# pCog100_Wifi_Sensor_uSD_TFT.net
KiCad netlist of a schematic drawn in EAGLE
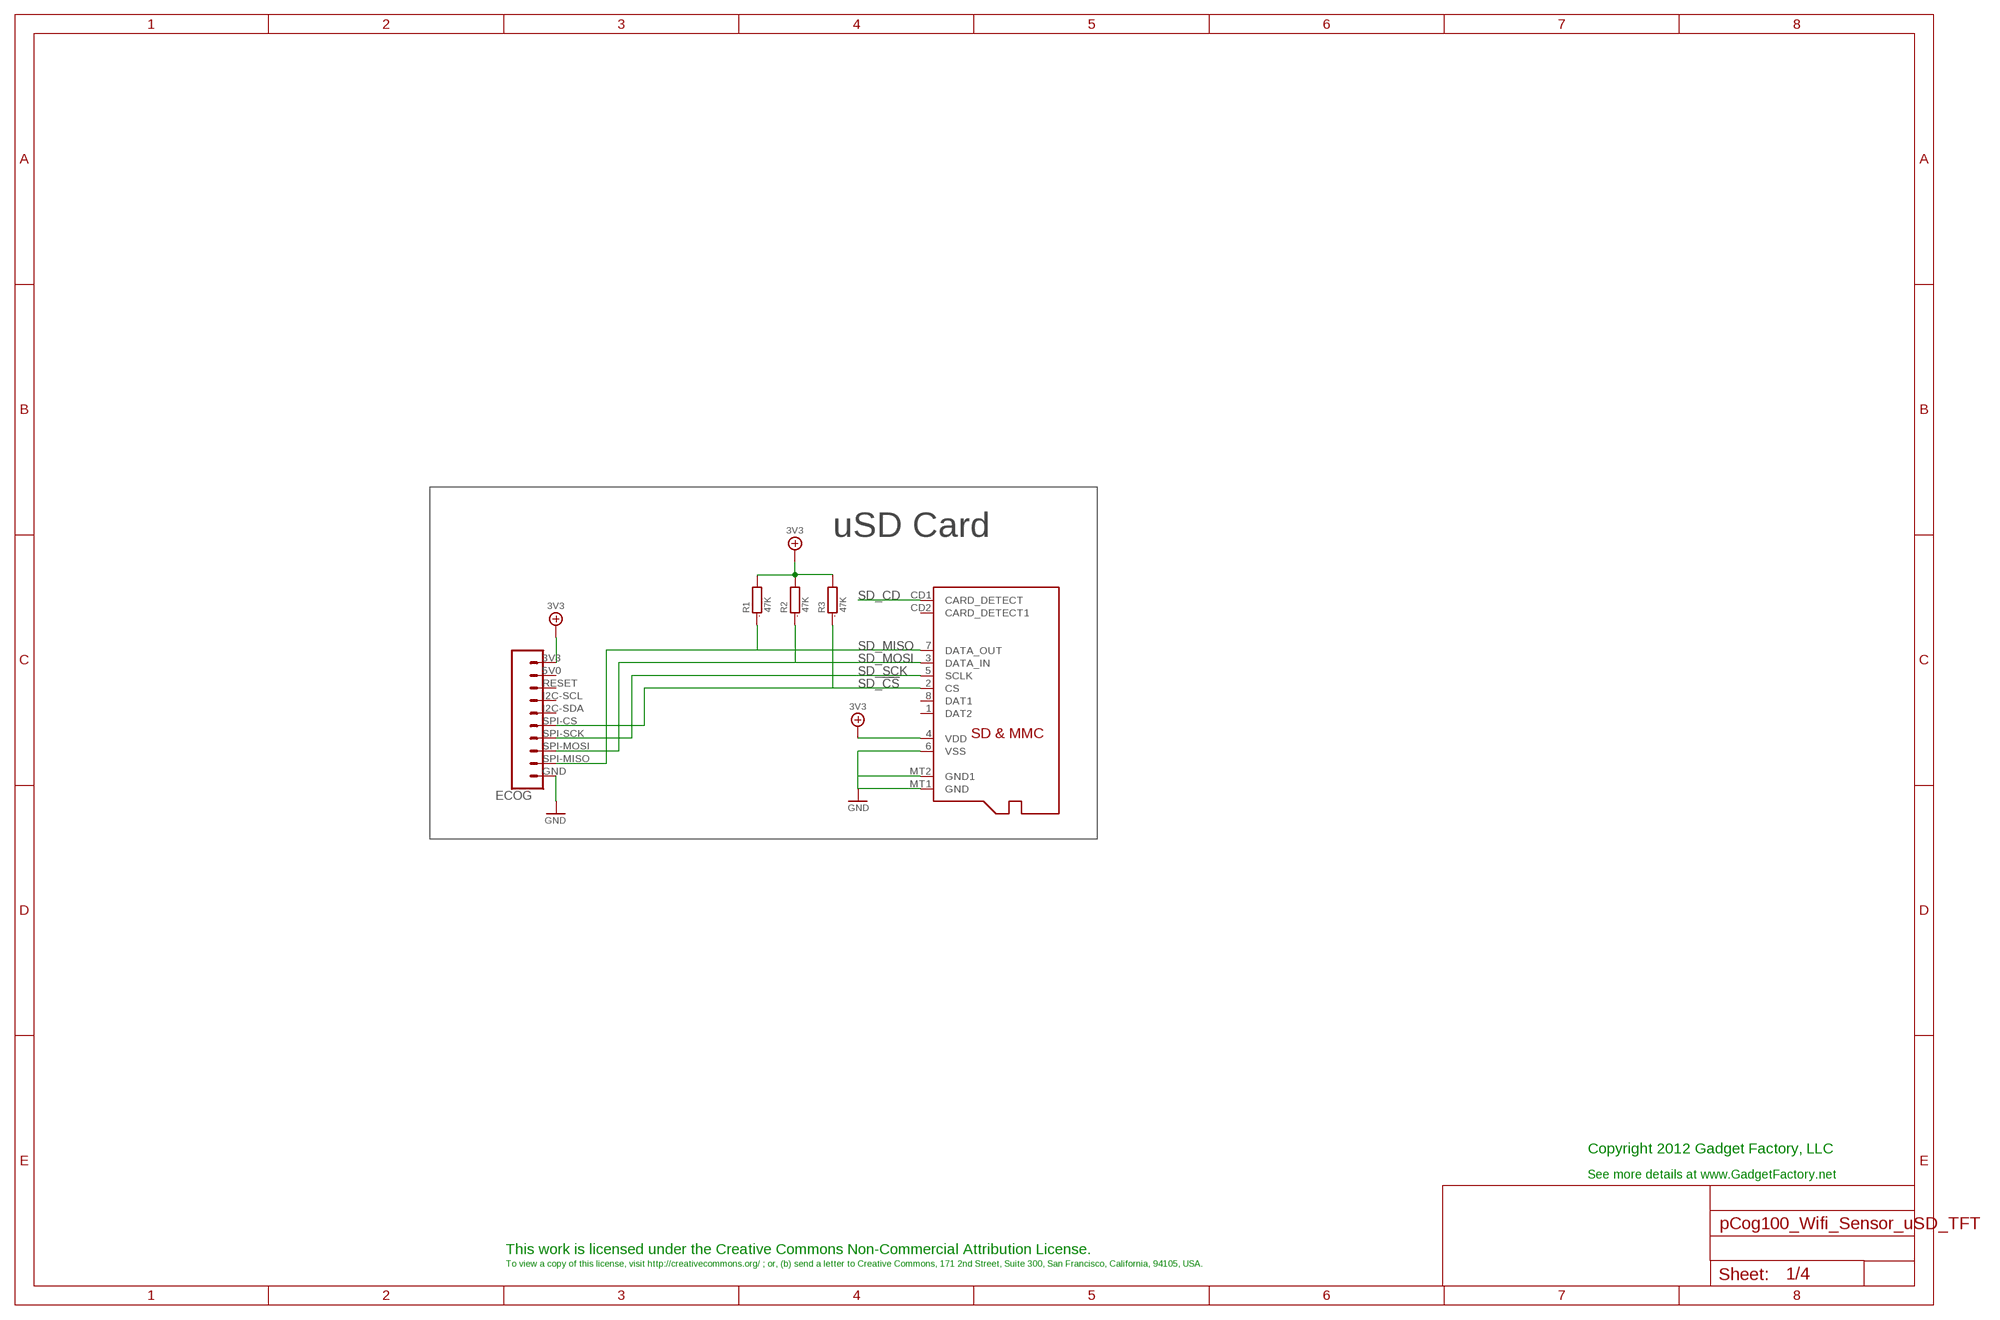
[diagram p0: schematic, sheet 1]
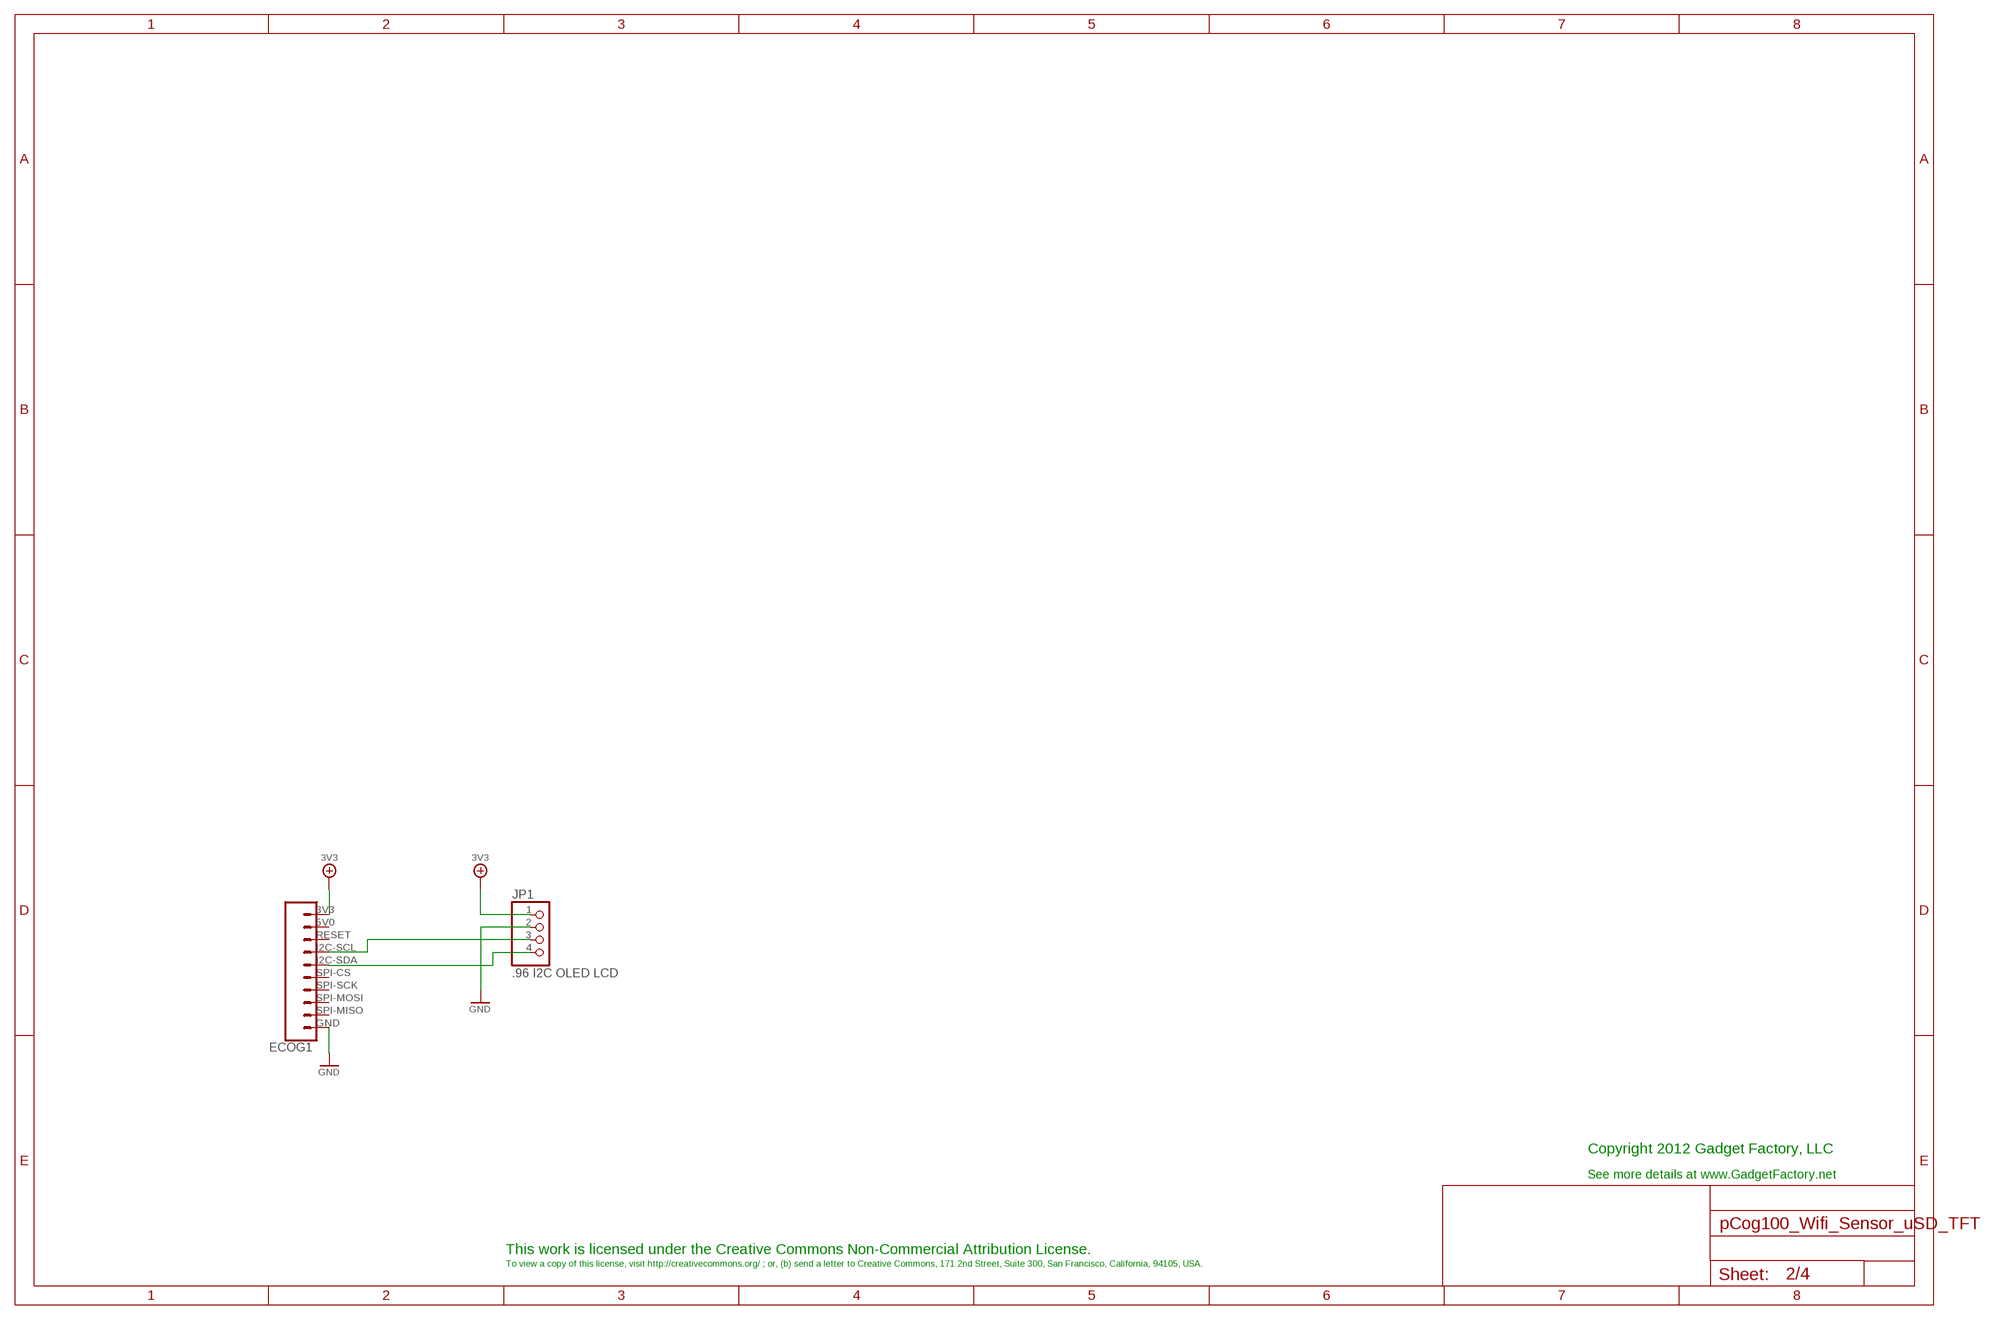
[diagram p1: schematic, sheet 2]
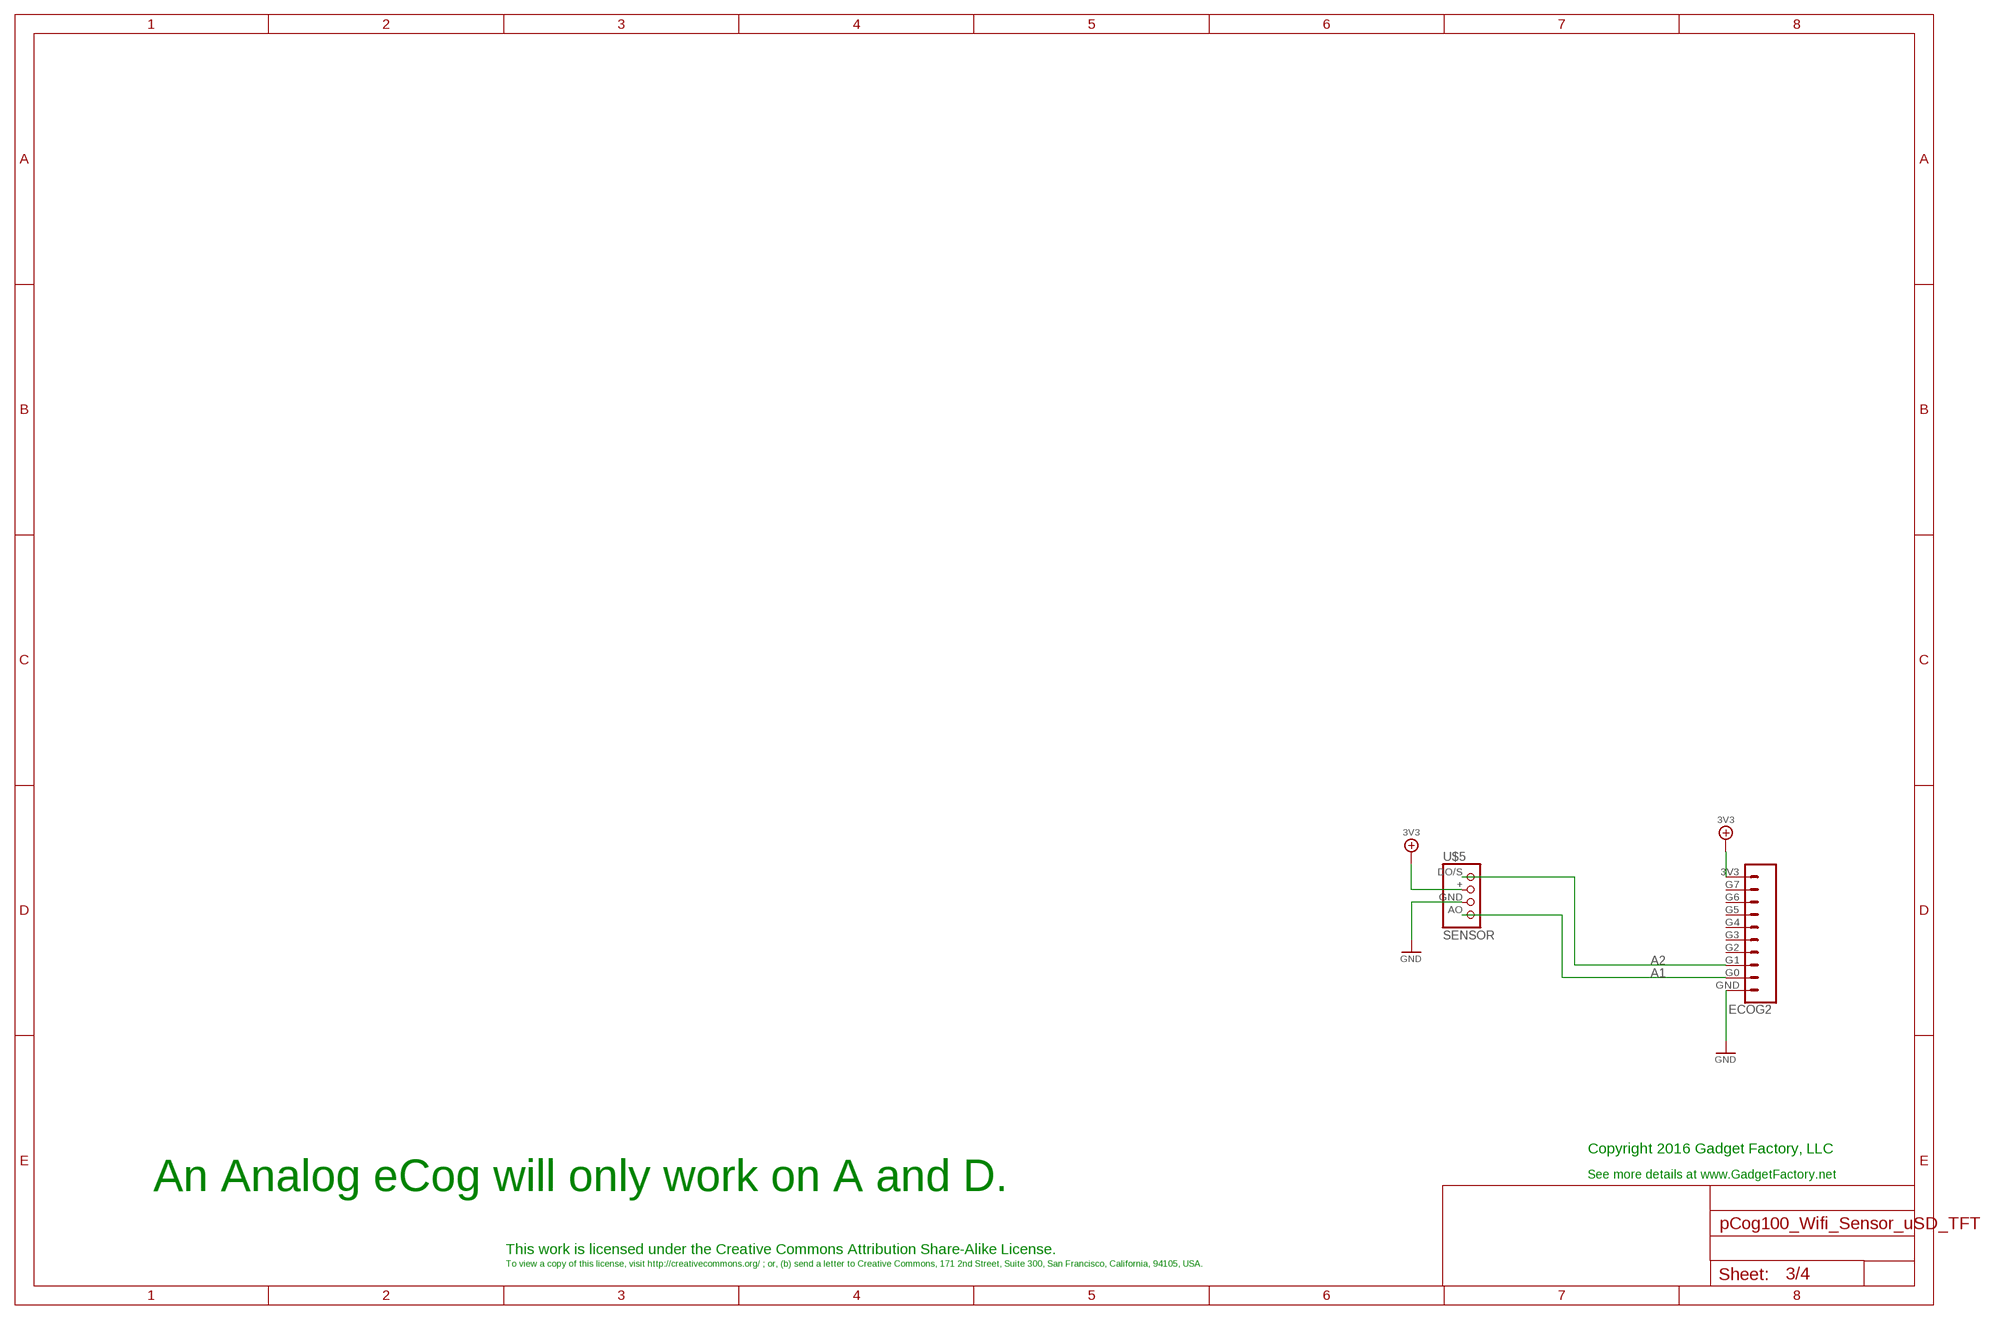
[diagram p2: schematic, sheet 3]
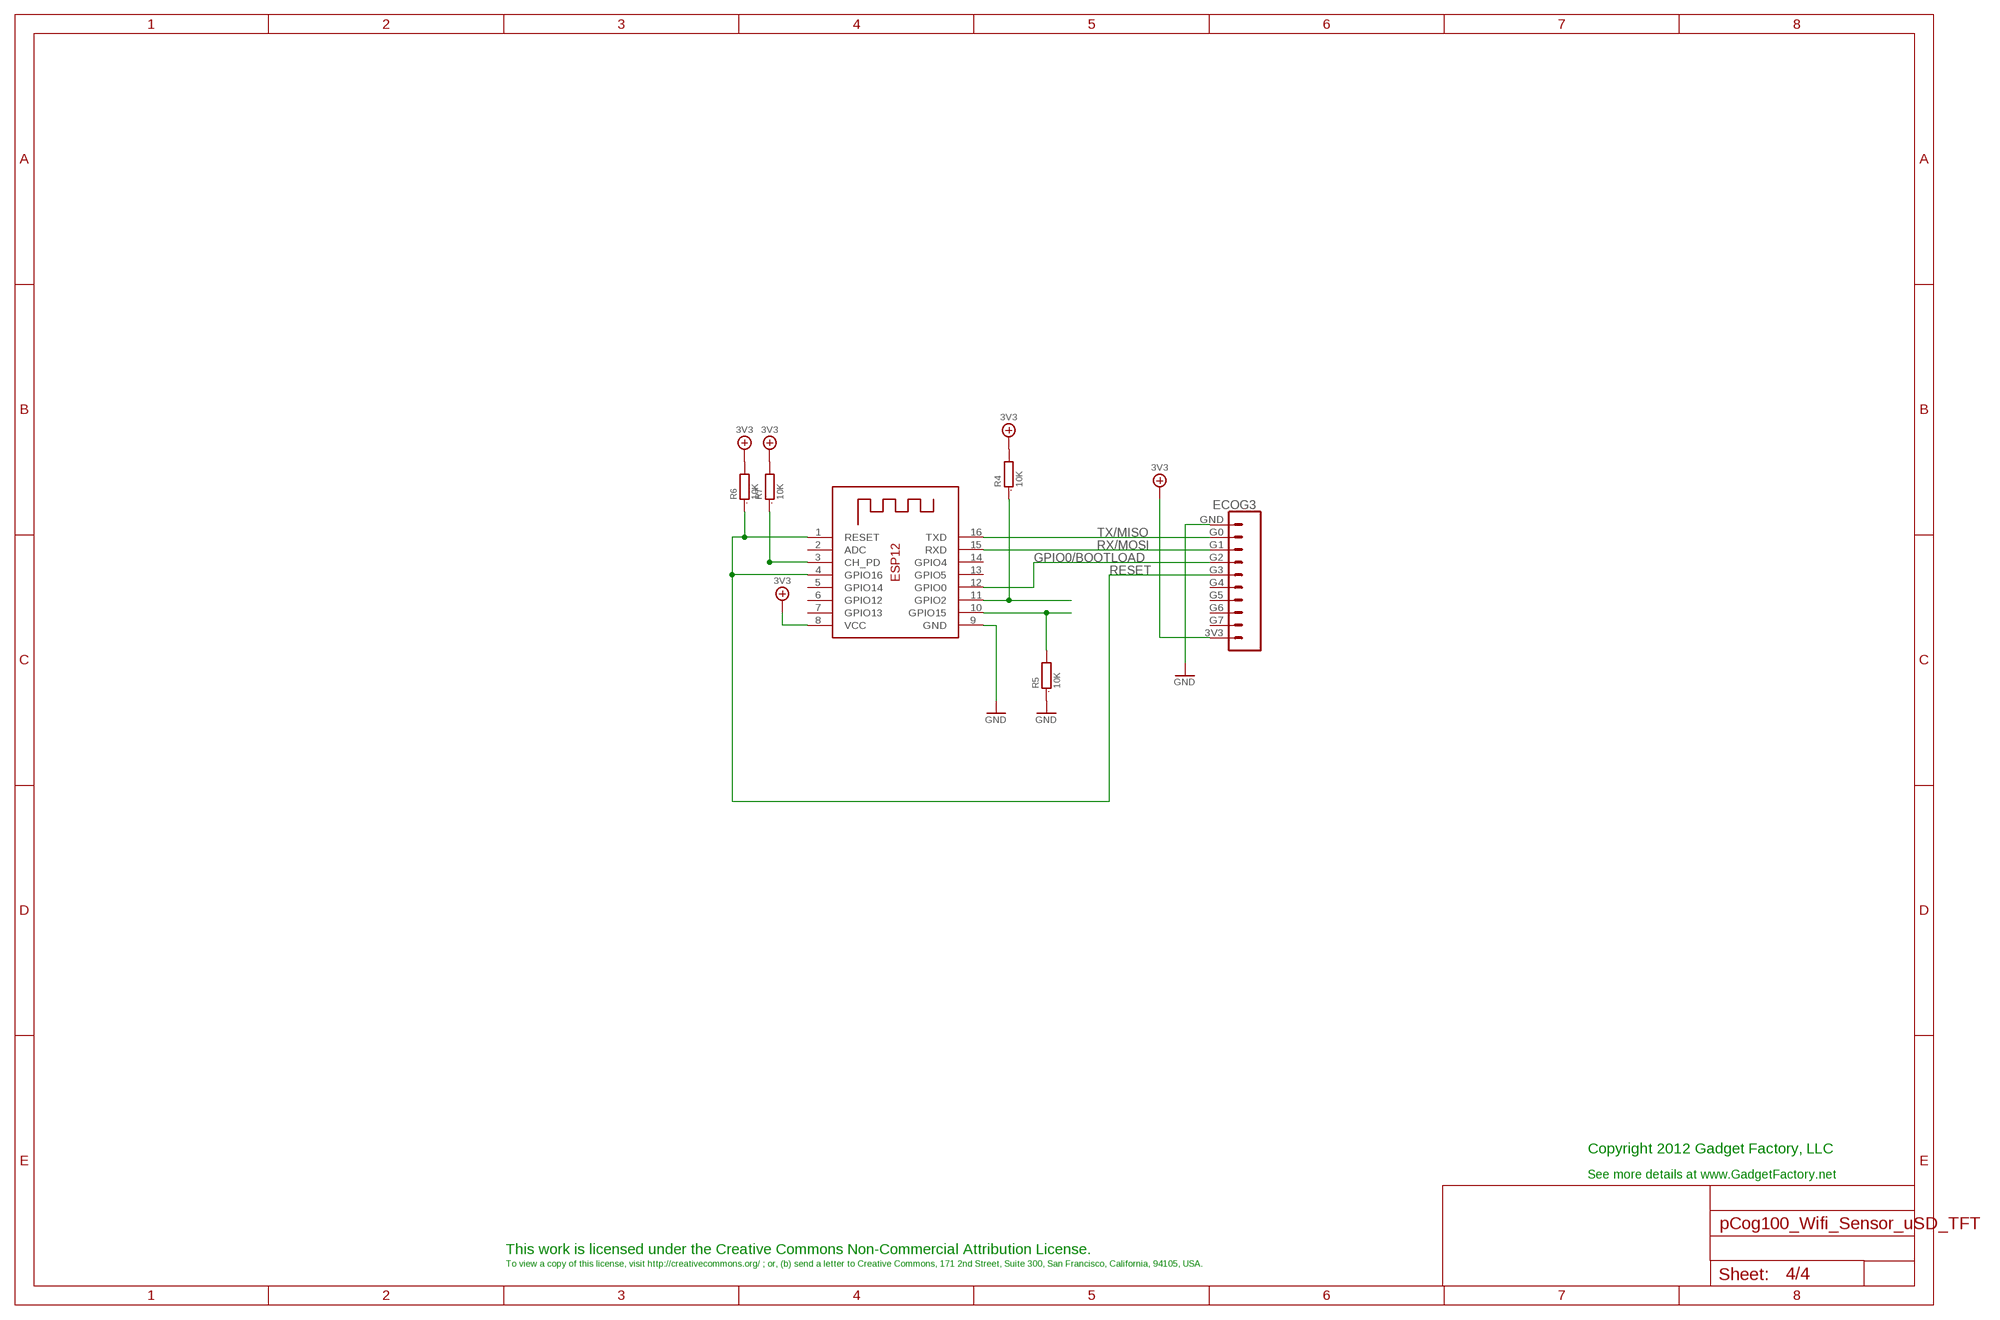
[diagram p3: schematic, sheet 4]

(export (version "E")
  (design (tool "Eeschema 10.0.6"))
  (components
    (comp (ref "ECOG3")
      (value "ECOG_GENERAL_ROWECOG_GENERAL_SMD")
      (footprint "eagle-import:ECOG_GENERAL_SMD")
      (libsource (lib "eagle-import") (part "ECOG_GENERAL_ROWECOG_GENERAL_SMD"))
    )
    (comp (ref "R4")
      (value "10K")
      (footprint "eagle-import:0805")
      (libsource (lib "eagle-import") (part "R0805"))
    )
    (comp (ref "R5")
      (value "10K")
      (footprint "eagle-import:0805")
      (libsource (lib "eagle-import") (part "R0805"))
    )
    (comp (ref "R6")
      (value "10K")
      (footprint "eagle-import:0805")
      (libsource (lib "eagle-import") (part "R0805"))
    )
    (comp (ref "R7")
      (value "10K")
      (footprint "eagle-import:0805")
      (libsource (lib "eagle-import") (part "R0805"))
    )
    (comp (ref "X1")
      (value "ESP-12")
      (footprint "eagle-import:ESP-12")
      (libsource (lib "eagle-import") (part "ESP-12"))
    )
    (comp (ref "ECOG1")
      (value "ECOG_BUSES_ROWECOG_BUSES_SMD")
      (footprint "eagle-import:ECOG_BUSES_SMD")
      (libsource (lib "eagle-import") (part "ECOG_BUSES_ROWECOG_BUSES_SMD"))
    )
    (comp (ref "JP1")
      (value ".96 I2C OLED LCD")
      (footprint "eagle-import:1X04")
      (libsource (lib "eagle-import") (part "PINHD-1X4"))
    )
    (comp (ref "ECOG2")
      (value "ECOG_GENERAL_ROWECOG_GENERAL_SMD")
      (footprint "eagle-import:ECOG_GENERAL_SMD")
      (libsource (lib "eagle-import") (part "ECOG_GENERAL_ROWECOG_GENERAL_SMD"))
    )
    (comp (ref "U$5")
      (value "SENSOR")
      (footprint "eagle-import:SENSOR-HJX4")
      (libsource (lib "eagle-import") (part "SENSOR"))
    )
    (comp (ref "ECOG")
      (value "ECOG_BUSES_ROWECOG_BUSES_SMD")
      (footprint "eagle-import:ECOG_BUSES_SMD")
      (libsource (lib "eagle-import") (part "ECOG_BUSES_ROWECOG_BUSES_SMD"))
    )
    (comp (ref "R1")
      (value "47K")
      (footprint "eagle-import:0805")
      (fields (field (name "PARTNO") "RMCF0805JT47K0"))
      (libsource (lib "eagle-import") (part "GadgetFactory_6.0_R0805"))
    )
    (comp (ref "R2")
      (value "47K")
      (footprint "eagle-import:0805")
      (fields (field (name "PARTNO") "RMCF0805JT47K0"))
      (libsource (lib "eagle-import") (part "GadgetFactory_6.0_R0805"))
    )
    (comp (ref "R3")
      (value "47K")
      (footprint "eagle-import:0805")
      (fields (field (name "PARTNO") "RMCF0805JT47K0"))
      (libsource (lib "eagle-import") (part "GadgetFactory_6.0_R0805"))
    )
    (comp (ref "SD1")
      (value "MICROSD")
      (footprint "eagle-import:MICROSD")
      (fields (field (name "DIGIKEY") "101-00660-68-6-1-ND") (field (name "PARTNO") "101-00660-68-6"))
      (libsource (lib "eagle-import") (part "MICROSD"))
    )
  )
  (nets
    (net (code "1") (name "3V3") (class "Default")
      (node (ref "ECOG") (pin "3V3") (pinfunction "3V3_3V3") (pintype "passive"))
      (node (ref "ECOG1") (pin "3V3") (pinfunction "3V3_3V3") (pintype "passive"))
      (node (ref "ECOG2") (pin "3V3") (pinfunction "3V3_3V3") (pintype "power_in"))
      (node (ref "ECOG3") (pin "3V3") (pinfunction "3V3_3V3") (pintype "power_in"))
      (node (ref "JP1") (pin "1") (pinfunction "1_1") (pintype "passive"))
      (node (ref "R1") (pin "2") (pinfunction "2_2") (pintype "passive"))
      (node (ref "R2") (pin "2") (pinfunction "2_2") (pintype "passive"))
      (node (ref "R3") (pin "2") (pinfunction "2_2") (pintype "passive"))
      (node (ref "R4") (pin "2") (pinfunction "2_2") (pintype "passive"))
      (node (ref "R6") (pin "2") (pinfunction "2_2") (pintype "passive"))
      (node (ref "R7") (pin "2") (pinfunction "2_2") (pintype "passive"))
      (node (ref "SD1") (pin "4") (pinfunction "VDD_4") (pintype "power_in"))
      (node (ref "U$5") (pin "+") (pinfunction "+_+") (pintype "passive"))
      (node (ref "X1") (pin "8") (pinfunction "VCC_8") (pintype "power_in"))
    )
    (net (code "2") (name "A1") (class "Default")
      (node (ref "ECOG2") (pin "G0") (pinfunction "G0_G0") (pintype "passive"))
      (node (ref "U$5") (pin "AO") (pinfunction "AO_AO") (pintype "passive"))
    )
    (net (code "3") (name "A2") (class "Default")
      (node (ref "ECOG2") (pin "G1") (pinfunction "G1_G1") (pintype "passive"))
      (node (ref "U$5") (pin "DO/S") (pinfunction "DO/S_DO/S") (pintype "passive"))
    )
    (net (code "4") (name "GND") (class "Default")
      (node (ref "ECOG") (pin "GND") (pinfunction "GND_GND") (pintype "passive"))
      (node (ref "ECOG1") (pin "GND") (pinfunction "GND_GND") (pintype "passive"))
      (node (ref "ECOG2") (pin "GND") (pinfunction "GND_GND") (pintype "power_in"))
      (node (ref "ECOG3") (pin "GND") (pinfunction "GND_GND") (pintype "power_in"))
      (node (ref "JP1") (pin "2") (pinfunction "2_2") (pintype "passive"))
      (node (ref "R5") (pin "1") (pinfunction "1_1") (pintype "passive"))
      (node (ref "SD1") (pin "6") (pinfunction "VSS_6") (pintype "power_in"))
      (node (ref "SD1") (pin "MT1") (pinfunction "GND_MT1") (pintype "power_in"))
      (node (ref "SD1") (pin "MT2") (pinfunction "GND1_MT2") (pintype "power_in"))
      (node (ref "U$5") (pin "GND") (pinfunction "GND_GND") (pintype "passive"))
      (node (ref "X1") (pin "9") (pinfunction "GND_9") (pintype "power_in"))
    )
    (net (code "5") (name "GPIO0{slash}BOOTLOAD") (class "Default")
      (node (ref "ECOG3") (pin "G2") (pinfunction "G2_G2") (pintype "passive"))
      (node (ref "X1") (pin "12") (pinfunction "GPIO0_12") (pintype "bidirectional"))
    )
    (net (code "6") (name "Net-(ECOG1-PadI2C-SCL)") (class "Default")
      (node (ref "ECOG1") (pin "I2C-SCL") (pinfunction "I2C-SCL_I2C-SCL") (pintype "passive"))
      (node (ref "JP1") (pin "3") (pinfunction "3_3") (pintype "passive"))
    )
    (net (code "7") (name "Net-(ECOG1-PadI2C-SDA)") (class "Default")
      (node (ref "ECOG1") (pin "I2C-SDA") (pinfunction "I2C-SDA_I2C-SDA") (pintype "passive"))
      (node (ref "JP1") (pin "4") (pinfunction "4_4") (pintype "passive"))
    )
    (net (code "8") (name "Net-(X1-CH_PD)") (class "Default")
      (node (ref "R7") (pin "1") (pinfunction "1_1") (pintype "passive"))
      (node (ref "X1") (pin "3") (pinfunction "CH_PD_3") (pintype "input"))
    )
    (net (code "9") (name "Net-(X1-GPIO2)") (class "Default")
      (node (ref "R4") (pin "1") (pinfunction "1_1") (pintype "passive"))
      (node (ref "X1") (pin "11") (pinfunction "GPIO2_11") (pintype "bidirectional"))
    )
    (net (code "10") (name "Net-(X1-GPIO15)") (class "Default")
      (node (ref "R5") (pin "2") (pinfunction "2_2") (pintype "passive"))
      (node (ref "X1") (pin "10") (pinfunction "GPIO15_10") (pintype "bidirectional"))
    )
    (net (code "11") (name "RESET") (class "Default")
      (node (ref "ECOG3") (pin "G3") (pinfunction "G3_G3") (pintype "passive"))
      (node (ref "R6") (pin "1") (pinfunction "1_1") (pintype "passive"))
      (node (ref "X1") (pin "1") (pinfunction "RESET_1") (pintype "input"))
      (node (ref "X1") (pin "4") (pinfunction "GPIO16_4") (pintype "bidirectional"))
    )
    (net (code "12") (name "RX{slash}MOSI") (class "Default")
      (node (ref "ECOG3") (pin "G1") (pinfunction "G1_G1") (pintype "passive"))
      (node (ref "X1") (pin "15") (pinfunction "RXD_15") (pintype "input"))
    )
    (net (code "13") (name "SD_CD") (class "Default")
      (node (ref "SD1") (pin "CD1") (pinfunction "CARD_DETECT_CD1") (pintype "passive"))
    )
    (net (code "14") (name "SD_MISO") (class "Default")
      (node (ref "ECOG") (pin "SPI-MISO") (pinfunction "SPI-MISO_SPI-MISO") (pintype "passive"))
      (node (ref "R1") (pin "1") (pinfunction "1_1") (pintype "passive"))
      (node (ref "SD1") (pin "7") (pinfunction "DATA_OUT_7") (pintype "output"))
    )
    (net (code "15") (name "SD_MOSI") (class "Default")
      (node (ref "ECOG") (pin "SPI-MOSI") (pinfunction "SPI-MOSI_SPI-MOSI") (pintype "passive"))
      (node (ref "R2") (pin "1") (pinfunction "1_1") (pintype "passive"))
      (node (ref "SD1") (pin "3") (pinfunction "DATA_IN_3") (pintype "input"))
    )
    (net (code "16") (name "SD_SCK") (class "Default")
      (node (ref "ECOG") (pin "SPI-SCK") (pinfunction "SPI-SCK_SPI-SCK") (pintype "passive"))
      (node (ref "SD1") (pin "5") (pinfunction "SCLK_5") (pintype "input"))
    )
    (net (code "17") (name "SD_~{CS}") (class "Default")
      (node (ref "ECOG") (pin "SPI-CS") (pinfunction "SPI-CS_SPI-CS") (pintype "passive"))
      (node (ref "R3") (pin "1") (pinfunction "1_1") (pintype "passive"))
      (node (ref "SD1") (pin "2") (pinfunction "CS_2") (pintype "input"))
    )
    (net (code "18") (name "TX{slash}MISO") (class "Default")
      (node (ref "ECOG3") (pin "G0") (pinfunction "G0_G0") (pintype "passive"))
      (node (ref "X1") (pin "16") (pinfunction "TXD_16") (pintype "output"))
    )
    (net (code "19") (name "unconnected-(ECOG-Pad5V0)") (class "Default")
      (node (ref "ECOG") (pin "5V0") (pinfunction "5V0_5V0") (pintype "passive"))
    )
    (net (code "20") (name "unconnected-(ECOG-PadI2C-SCL)") (class "Default")
      (node (ref "ECOG") (pin "I2C-SCL") (pinfunction "I2C-SCL_I2C-SCL") (pintype "passive"))
    )
    (net (code "21") (name "unconnected-(ECOG-PadI2C-SDA)") (class "Default")
      (node (ref "ECOG") (pin "I2C-SDA") (pinfunction "I2C-SDA_I2C-SDA") (pintype "passive"))
    )
    (net (code "22") (name "unconnected-(ECOG-PadRESET)") (class "Default")
      (node (ref "ECOG") (pin "RESET") (pinfunction "RESET_RESET") (pintype "passive"))
    )
    (net (code "23") (name "unconnected-(ECOG1-Pad5V0)") (class "Default")
      (node (ref "ECOG1") (pin "5V0") (pinfunction "5V0_5V0") (pintype "passive"))
    )
    (net (code "24") (name "unconnected-(ECOG1-PadRESET)") (class "Default")
      (node (ref "ECOG1") (pin "RESET") (pinfunction "RESET_RESET") (pintype "passive"))
    )
    (net (code "25") (name "unconnected-(ECOG1-PadSPI-CS)") (class "Default")
      (node (ref "ECOG1") (pin "SPI-CS") (pinfunction "SPI-CS_SPI-CS") (pintype "passive"))
    )
    (net (code "26") (name "unconnected-(ECOG1-PadSPI-MISO)") (class "Default")
      (node (ref "ECOG1") (pin "SPI-MISO") (pinfunction "SPI-MISO_SPI-MISO") (pintype "passive"))
    )
    (net (code "27") (name "unconnected-(ECOG1-PadSPI-MOSI)") (class "Default")
      (node (ref "ECOG1") (pin "SPI-MOSI") (pinfunction "SPI-MOSI_SPI-MOSI") (pintype "passive"))
    )
    (net (code "28") (name "unconnected-(ECOG1-PadSPI-SCK)") (class "Default")
      (node (ref "ECOG1") (pin "SPI-SCK") (pinfunction "SPI-SCK_SPI-SCK") (pintype "passive"))
    )
    (net (code "29") (name "unconnected-(ECOG2-PadG2)") (class "Default")
      (node (ref "ECOG2") (pin "G2") (pinfunction "G2_G2") (pintype "passive"))
    )
    (net (code "30") (name "unconnected-(ECOG2-PadG3)") (class "Default")
      (node (ref "ECOG2") (pin "G3") (pinfunction "G3_G3") (pintype "passive"))
    )
    (net (code "31") (name "unconnected-(ECOG2-PadG4)") (class "Default")
      (node (ref "ECOG2") (pin "G4") (pinfunction "G4_G4") (pintype "passive"))
    )
    (net (code "32") (name "unconnected-(ECOG2-PadG5)") (class "Default")
      (node (ref "ECOG2") (pin "G5") (pinfunction "G5_G5") (pintype "passive"))
    )
    (net (code "33") (name "unconnected-(ECOG2-PadG6)") (class "Default")
      (node (ref "ECOG2") (pin "G6") (pinfunction "G6_G6") (pintype "passive"))
    )
    (net (code "34") (name "unconnected-(ECOG2-PadG7)") (class "Default")
      (node (ref "ECOG2") (pin "G7") (pinfunction "G7_G7") (pintype "passive"))
    )
    (net (code "35") (name "unconnected-(ECOG3-PadG4)") (class "Default")
      (node (ref "ECOG3") (pin "G4") (pinfunction "G4_G4") (pintype "passive"))
    )
    (net (code "36") (name "unconnected-(ECOG3-PadG5)") (class "Default")
      (node (ref "ECOG3") (pin "G5") (pinfunction "G5_G5") (pintype "passive"))
    )
    (net (code "37") (name "unconnected-(ECOG3-PadG6)") (class "Default")
      (node (ref "ECOG3") (pin "G6") (pinfunction "G6_G6") (pintype "passive"))
    )
    (net (code "38") (name "unconnected-(ECOG3-PadG7)") (class "Default")
      (node (ref "ECOG3") (pin "G7") (pinfunction "G7_G7") (pintype "passive"))
    )
    (net (code "39") (name "unconnected-(SD1-CARD_DETECT1-PadCD2)") (class "Default")
      (node (ref "SD1") (pin "CD2") (pinfunction "CARD_DETECT1_CD2") (pintype "passive"))
    )
    (net (code "40") (name "unconnected-(SD1-DAT1-Pad8)") (class "Default")
      (node (ref "SD1") (pin "8") (pinfunction "DAT1_8") (pintype "bidirectional"))
    )
    (net (code "41") (name "unconnected-(SD1-DAT2-Pad1)") (class "Default")
      (node (ref "SD1") (pin "1") (pinfunction "DAT2_1") (pintype "bidirectional"))
    )
    (net (code "42") (name "unconnected-(X1-ADC-Pad2)") (class "Default")
      (node (ref "X1") (pin "2") (pinfunction "ADC_2") (pintype "passive"))
    )
    (net (code "43") (name "unconnected-(X1-GPIO4-Pad14)") (class "Default")
      (node (ref "X1") (pin "14") (pinfunction "GPIO4_14") (pintype "bidirectional"))
    )
    (net (code "44") (name "unconnected-(X1-GPIO5-Pad13)") (class "Default")
      (node (ref "X1") (pin "13") (pinfunction "GPIO5_13") (pintype "bidirectional"))
    )
    (net (code "45") (name "unconnected-(X1-GPIO12-Pad6)") (class "Default")
      (node (ref "X1") (pin "6") (pinfunction "GPIO12_6") (pintype "bidirectional"))
    )
    (net (code "46") (name "unconnected-(X1-GPIO13-Pad7)") (class "Default")
      (node (ref "X1") (pin "7") (pinfunction "GPIO13_7") (pintype "bidirectional"))
    )
    (net (code "47") (name "unconnected-(X1-GPIO14-Pad5)") (class "Default")
      (node (ref "X1") (pin "5") (pinfunction "GPIO14_5") (pintype "bidirectional"))
    )
  )
)
